# ISO_COMMS.net
KiCad netlist of a schematic drawn in Altium Designer
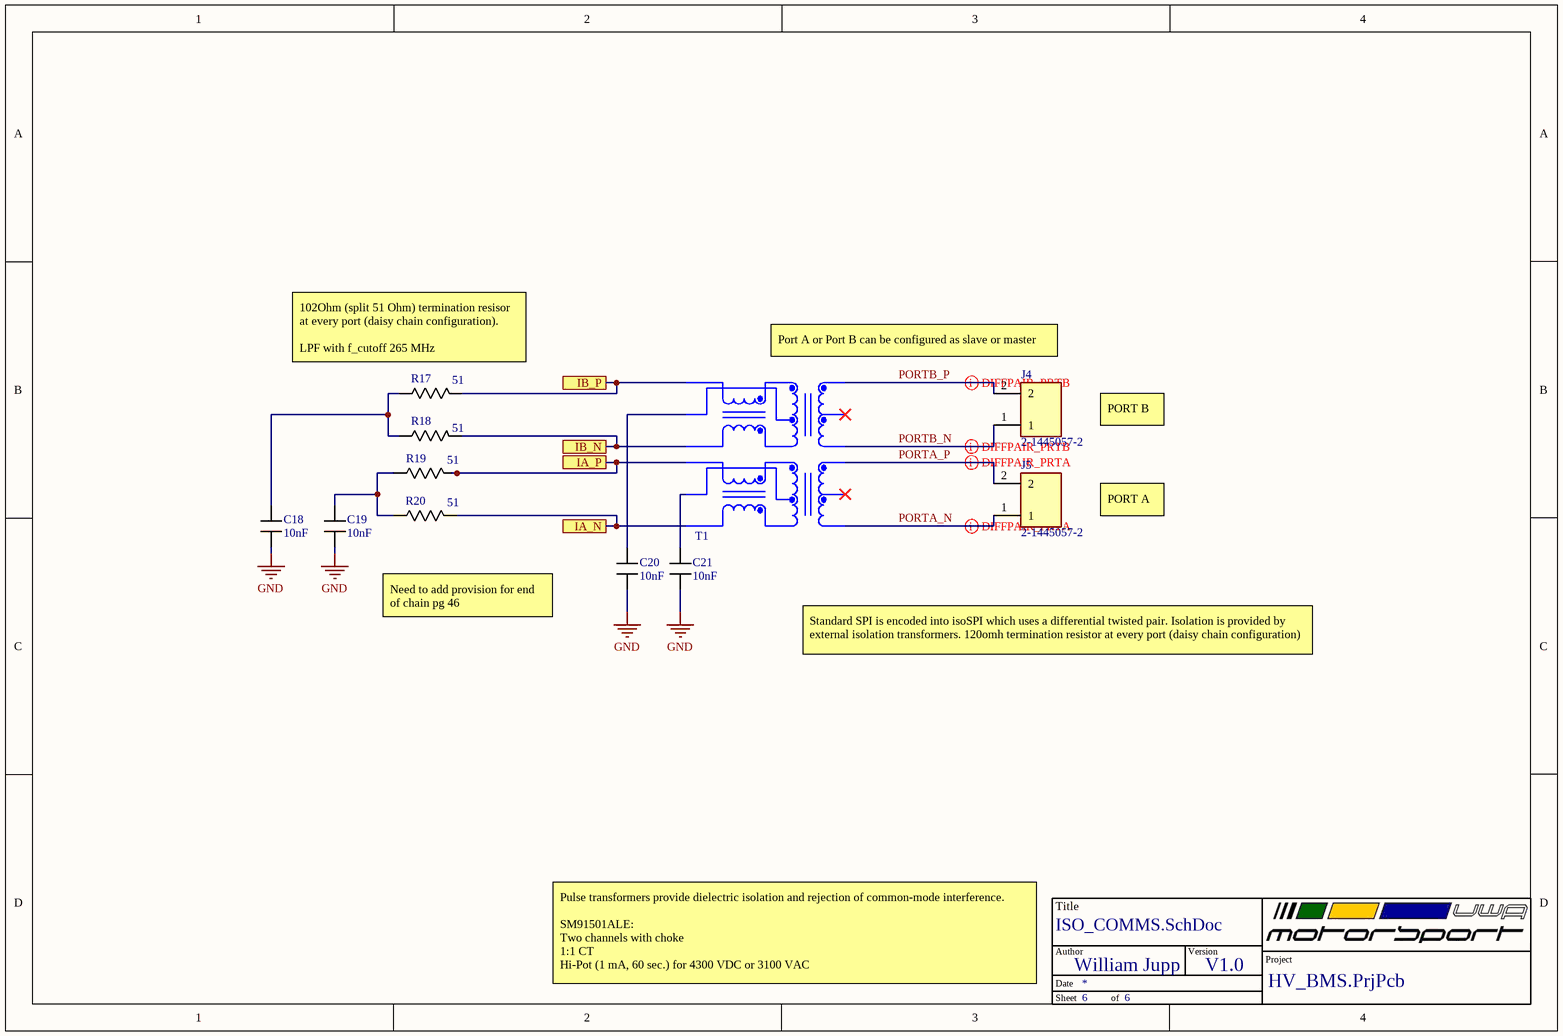
[diagram p0: ISO_COMMS.SchDoc]

(export (version "E")
  (design (tool "Eeschema 10.0.6"))
  (components
    (comp (ref "C18")
      (value "10nF")
      (footprint "C_0603")
      (description "Capacitor")
      (fields (field (name "Comment") "C"))
      (libsource (lib "Passives") (part "Capacitor"))
    )
    (comp (ref "C19")
      (value "10nF")
      (footprint "C_0603")
      (description "Capacitor")
      (fields (field (name "Comment") "C"))
      (libsource (lib "Passives") (part "Capacitor"))
    )
    (comp (ref "C20")
      (value "10nF")
      (footprint "C_0603")
      (description "Capacitor")
      (fields (field (name "Comment") "C"))
      (libsource (lib "Passives") (part "Capacitor"))
    )
    (comp (ref "C21")
      (value "10nF")
      (footprint "C_0603")
      (description "Capacitor")
      (fields (field (name "Comment") "C"))
      (libsource (lib "Passives") (part "Capacitor"))
    )
    (comp (ref "J4")
      (value "2-1445057-2")
      (footprint "TE_2-1445057-2")
      (description "CONN HEADER 3MM 2POS R/A TIN SMD--")
      (fields (field (name "MF") "{'manufacturer': u'TE Connectivity'}"))
      (libsource (lib "SnapEDA_Library") (part "2-1445057-2"))
    )
    (comp (ref "J5")
      (value "2-1445057-2")
      (footprint "TE_2-1445057-2")
      (description "CONN HEADER 3MM 2POS R/A TIN SMD")
      (fields (field (name "MF") "{'manufacturer': u'TE Connectivity'}"))
      (libsource (lib "SnapEDA_Library") (part "2-1445057-2"))
    )
    (comp (ref "R17")
      (value "51")
      (footprint "R-0603")
      (description "Resistor")
      (libsource (lib "Passives") (part "Resistor"))
    )
    (comp (ref "R18")
      (value "51")
      (footprint "R-0603")
      (description "Resistor")
      (libsource (lib "Passives") (part "Resistor"))
    )
    (comp (ref "R19")
      (value "51")
      (footprint "R-0603")
      (description "Resistor")
      (libsource (lib "Passives") (part "Resistor"))
    )
    (comp (ref "R20")
      (value "51")
      (footprint "R-0603")
      (description "Resistor")
      (libsource (lib "Passives") (part "Resistor"))
    )
    (comp (ref "T1")
      (value "SM91501ALE")
      (footprint "SM91501ALE")
      (description "BMS XFORMER 2-CH 1600V AECQ +125")
      (fields (field (name "MANUFACTURER") "Bourns"))
      (libsource (lib "HV_BMS_SCH_LIB") (part "SM91501ALE"))
    )
  )
  (nets
    (net (code "1") (name "/IA_N") (class "Default")
      (node (ref "R20") (pin "1") (pinfunction "1_1") (pintype "passive"))
      (node (ref "T1") (pin "7") (pinfunction "7_7") (pintype "passive"))
    )
    (net (code "2") (name "/IA_P") (class "Default")
      (node (ref "R19") (pin "2") (pinfunction "2_2") (pintype "passive"))
      (node (ref "T1") (pin "9") (pinfunction "9_9") (pintype "passive"))
    )
    (net (code "3") (name "/IB_N") (class "Default")
      (node (ref "R18") (pin "1") (pinfunction "1_1") (pintype "passive"))
      (node (ref "T1") (pin "10") (pinfunction "10_10") (pintype "passive"))
    )
    (net (code "4") (name "/IB_P") (class "Default")
      (node (ref "R17") (pin "2") (pinfunction "2_2") (pintype "passive"))
      (node (ref "T1") (pin "12") (pinfunction "12_12") (pintype "passive"))
    )
    (net (code "5") (name "/PORTA_N") (class "Default")
      (node (ref "J5") (pin "1") (pinfunction "1_1") (pintype "passive"))
      (node (ref "T1") (pin "6") (pinfunction "6_6") (pintype "passive"))
    )
    (net (code "6") (name "/PORTA_P") (class "Default")
      (node (ref "J5") (pin "2") (pinfunction "2_2") (pintype "passive"))
      (node (ref "T1") (pin "4") (pinfunction "4_4") (pintype "passive"))
    )
    (net (code "7") (name "/PORTB_N") (class "Default")
      (node (ref "J4") (pin "1") (pinfunction "1_1") (pintype "passive"))
      (node (ref "T1") (pin "3") (pinfunction "3_3") (pintype "passive"))
    )
    (net (code "8") (name "/PORTB_P") (class "Default")
      (node (ref "J4") (pin "2") (pinfunction "2_2") (pintype "passive"))
      (node (ref "T1") (pin "1") (pinfunction "1_1") (pintype "passive"))
    )
    (net (code "9") (name "GND") (class "Default")
      (node (ref "C18") (pin "1") (pinfunction "1_1") (pintype "passive"))
      (node (ref "C19") (pin "1") (pinfunction "1_1") (pintype "passive"))
      (node (ref "C20") (pin "2") (pinfunction "2_2") (pintype "passive"))
      (node (ref "C21") (pin "1") (pinfunction "1_1") (pintype "passive"))
    )
    (net (code "10") (name "Net-(C18-Pad2)") (class "Default")
      (node (ref "C18") (pin "2") (pinfunction "2_2") (pintype "passive"))
      (node (ref "R17") (pin "1") (pinfunction "1_1") (pintype "passive"))
      (node (ref "R18") (pin "2") (pinfunction "2_2") (pintype "passive"))
    )
    (net (code "11") (name "Net-(C19-Pad2)") (class "Default")
      (node (ref "C19") (pin "2") (pinfunction "2_2") (pintype "passive"))
      (node (ref "R19") (pin "1") (pinfunction "1_1") (pintype "passive"))
      (node (ref "R20") (pin "2") (pinfunction "2_2") (pintype "passive"))
    )
    (net (code "12") (name "Net-(C20-Pad1)") (class "Default")
      (node (ref "C20") (pin "1") (pinfunction "1_1") (pintype "passive"))
      (node (ref "T1") (pin "11") (pinfunction "11_11") (pintype "passive"))
    )
    (net (code "13") (name "Net-(C21-Pad2)") (class "Default")
      (node (ref "C21") (pin "2") (pinfunction "2_2") (pintype "passive"))
      (node (ref "T1") (pin "8") (pinfunction "8_8") (pintype "passive"))
    )
    (net (code "14") (name "unconnected-(T1-Pad2)") (class "Default")
      (node (ref "T1") (pin "2") (pinfunction "2_2") (pintype "passive+no_connect"))
    )
    (net (code "15") (name "unconnected-(T1-Pad5)") (class "Default")
      (node (ref "T1") (pin "5") (pinfunction "5_5") (pintype "passive+no_connect"))
    )
  )
)
